# powersupply.net
KiCad netlist of a schematic drawn in EAGLE
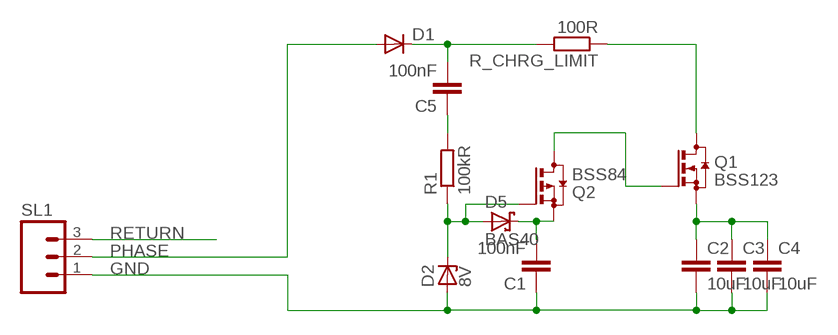
[diagram p0: schematic, sheet 1]

(export (version "E")
  (design (tool "Eeschema 10.0.6"))
  (components
    (comp (ref "C1")
      (value "100nF")
      (footprint "eagle-import:C0603")
      (libsource (lib "eagle-import") (part "C-EUC0603"))
    )
    (comp (ref "C2")
      (value "10uF")
      (footprint "eagle-import:C0805")
      (libsource (lib "eagle-import") (part "C-EUC0805"))
    )
    (comp (ref "C3")
      (value "10uF")
      (footprint "eagle-import:C0805")
      (libsource (lib "eagle-import") (part "C-EUC0805"))
    )
    (comp (ref "C4")
      (value "10uF")
      (footprint "eagle-import:C0805")
      (libsource (lib "eagle-import") (part "C-EUC0805"))
    )
    (comp (ref "C5")
      (value "100nF")
      (footprint "eagle-import:C0603")
      (libsource (lib "eagle-import") (part "C-EUC0603"))
    )
    (comp (ref "D1")
      (value "DIODE-DO214AA")
      (footprint "eagle-import:DO214AA")
      (libsource (lib "eagle-import") (part "DIODE-DO214AA"))
    )
    (comp (ref "D2")
      (value "8V")
      (footprint "eagle-import:SOD80C")
      (libsource (lib "eagle-import") (part "ZENER-DIODESOD80C"))
    )
    (comp (ref "D5")
      (value "BAS40")
      (footprint "eagle-import:SOT23")
      (libsource (lib "eagle-import") (part "BAS40"))
    )
    (comp (ref "Q1")
      (value "BSS123")
      (footprint "eagle-import:SOT23")
      (libsource (lib "eagle-import") (part "BSS123"))
    )
    (comp (ref "Q2")
      (value "BSS84")
      (footprint "eagle-import:SOT23")
      (libsource (lib "eagle-import") (part "BSS84"))
    )
    (comp (ref "R1")
      (value "100kR")
      (footprint "eagle-import:R0603")
      (libsource (lib "eagle-import") (part "R-EU_R0603"))
    )
    (comp (ref "R_CHRG_LIMIT")
      (value "100R")
      (footprint "eagle-import:R0603")
      (libsource (lib "eagle-import") (part "R-EU_R0603"))
    )
    (comp (ref "SL1")
      (value "M03")
      (footprint "eagle-import:03P")
      (libsource (lib "eagle-import") (part "M03"))
    )
  )
  (nets
    (net (code "1") (name "/GND") (class "Default")
      (node (ref "C1") (pin "1") (pinfunction "1_1") (pintype "passive"))
      (node (ref "C2") (pin "2") (pinfunction "2_2") (pintype "passive"))
      (node (ref "C3") (pin "2") (pinfunction "2_2") (pintype "passive"))
      (node (ref "C4") (pin "2") (pinfunction "2_2") (pintype "passive"))
      (node (ref "D2") (pin "A") (pinfunction "A_A") (pintype "passive"))
      (node (ref "SL1") (pin "1") (pinfunction "1_1") (pintype "passive"))
    )
    (net (code "2") (name "/PHASE") (class "Default")
      (node (ref "D1") (pin "A") (pinfunction "A_A") (pintype "passive"))
      (node (ref "SL1") (pin "2") (pinfunction "2_2") (pintype "passive"))
    )
    (net (code "3") (name "/RETURN") (class "Default")
      (node (ref "SL1") (pin "3") (pinfunction "3_3") (pintype "passive"))
    )
    (net (code "4") (name "Net-(C5-Pad1)") (class "Default")
      (node (ref "C5") (pin "1") (pinfunction "1_1") (pintype "passive"))
      (node (ref "R1") (pin "2") (pinfunction "2_2") (pintype "passive"))
    )
    (net (code "5") (name "Net-(C5-Pad2)") (class "Default")
      (node (ref "C5") (pin "2") (pinfunction "2_2") (pintype "passive"))
      (node (ref "D1") (pin "C") (pinfunction "C_C") (pintype "passive"))
      (node (ref "R_CHRG_LIMIT") (pin "2") (pinfunction "2_2") (pintype "passive"))
    )
    (net (code "6") (name "Net-(D5-A)") (class "Default")
      (node (ref "D2") (pin "C") (pinfunction "C_C") (pintype "passive"))
      (node (ref "D5") (pin "1") (pinfunction "A_1") (pintype "passive"))
      (node (ref "Q2") (pin "1") (pinfunction "G_1") (pintype "passive"))
      (node (ref "R1") (pin "1") (pinfunction "1_1") (pintype "passive"))
    )
    (net (code "7") (name "Net-(D5-C)") (class "Default")
      (node (ref "C1") (pin "2") (pinfunction "2_2") (pintype "passive"))
      (node (ref "D5") (pin "3") (pinfunction "C_3") (pintype "passive"))
      (node (ref "Q2") (pin "2") (pinfunction "S_2") (pintype "passive"))
    )
    (net (code "8") (name "Net-(Q1-D)") (class "Default")
      (node (ref "Q1") (pin "3") (pinfunction "D_3") (pintype "passive"))
      (node (ref "R_CHRG_LIMIT") (pin "1") (pinfunction "1_1") (pintype "passive"))
    )
    (net (code "9") (name "Net-(Q1-G)") (class "Default")
      (node (ref "Q1") (pin "1") (pinfunction "G_1") (pintype "passive"))
      (node (ref "Q2") (pin "3") (pinfunction "D_3") (pintype "passive"))
    )
    (net (code "10") (name "Net-(Q1-S)") (class "Default")
      (node (ref "C2") (pin "1") (pinfunction "1_1") (pintype "passive"))
      (node (ref "C3") (pin "1") (pinfunction "1_1") (pintype "passive"))
      (node (ref "C4") (pin "1") (pinfunction "1_1") (pintype "passive"))
      (node (ref "Q1") (pin "2") (pinfunction "S_2") (pintype "passive"))
    )
  )
)
